# bpf-L-band-BPF-A1340.net
KiCad netlist of a schematic drawn in EAGLE
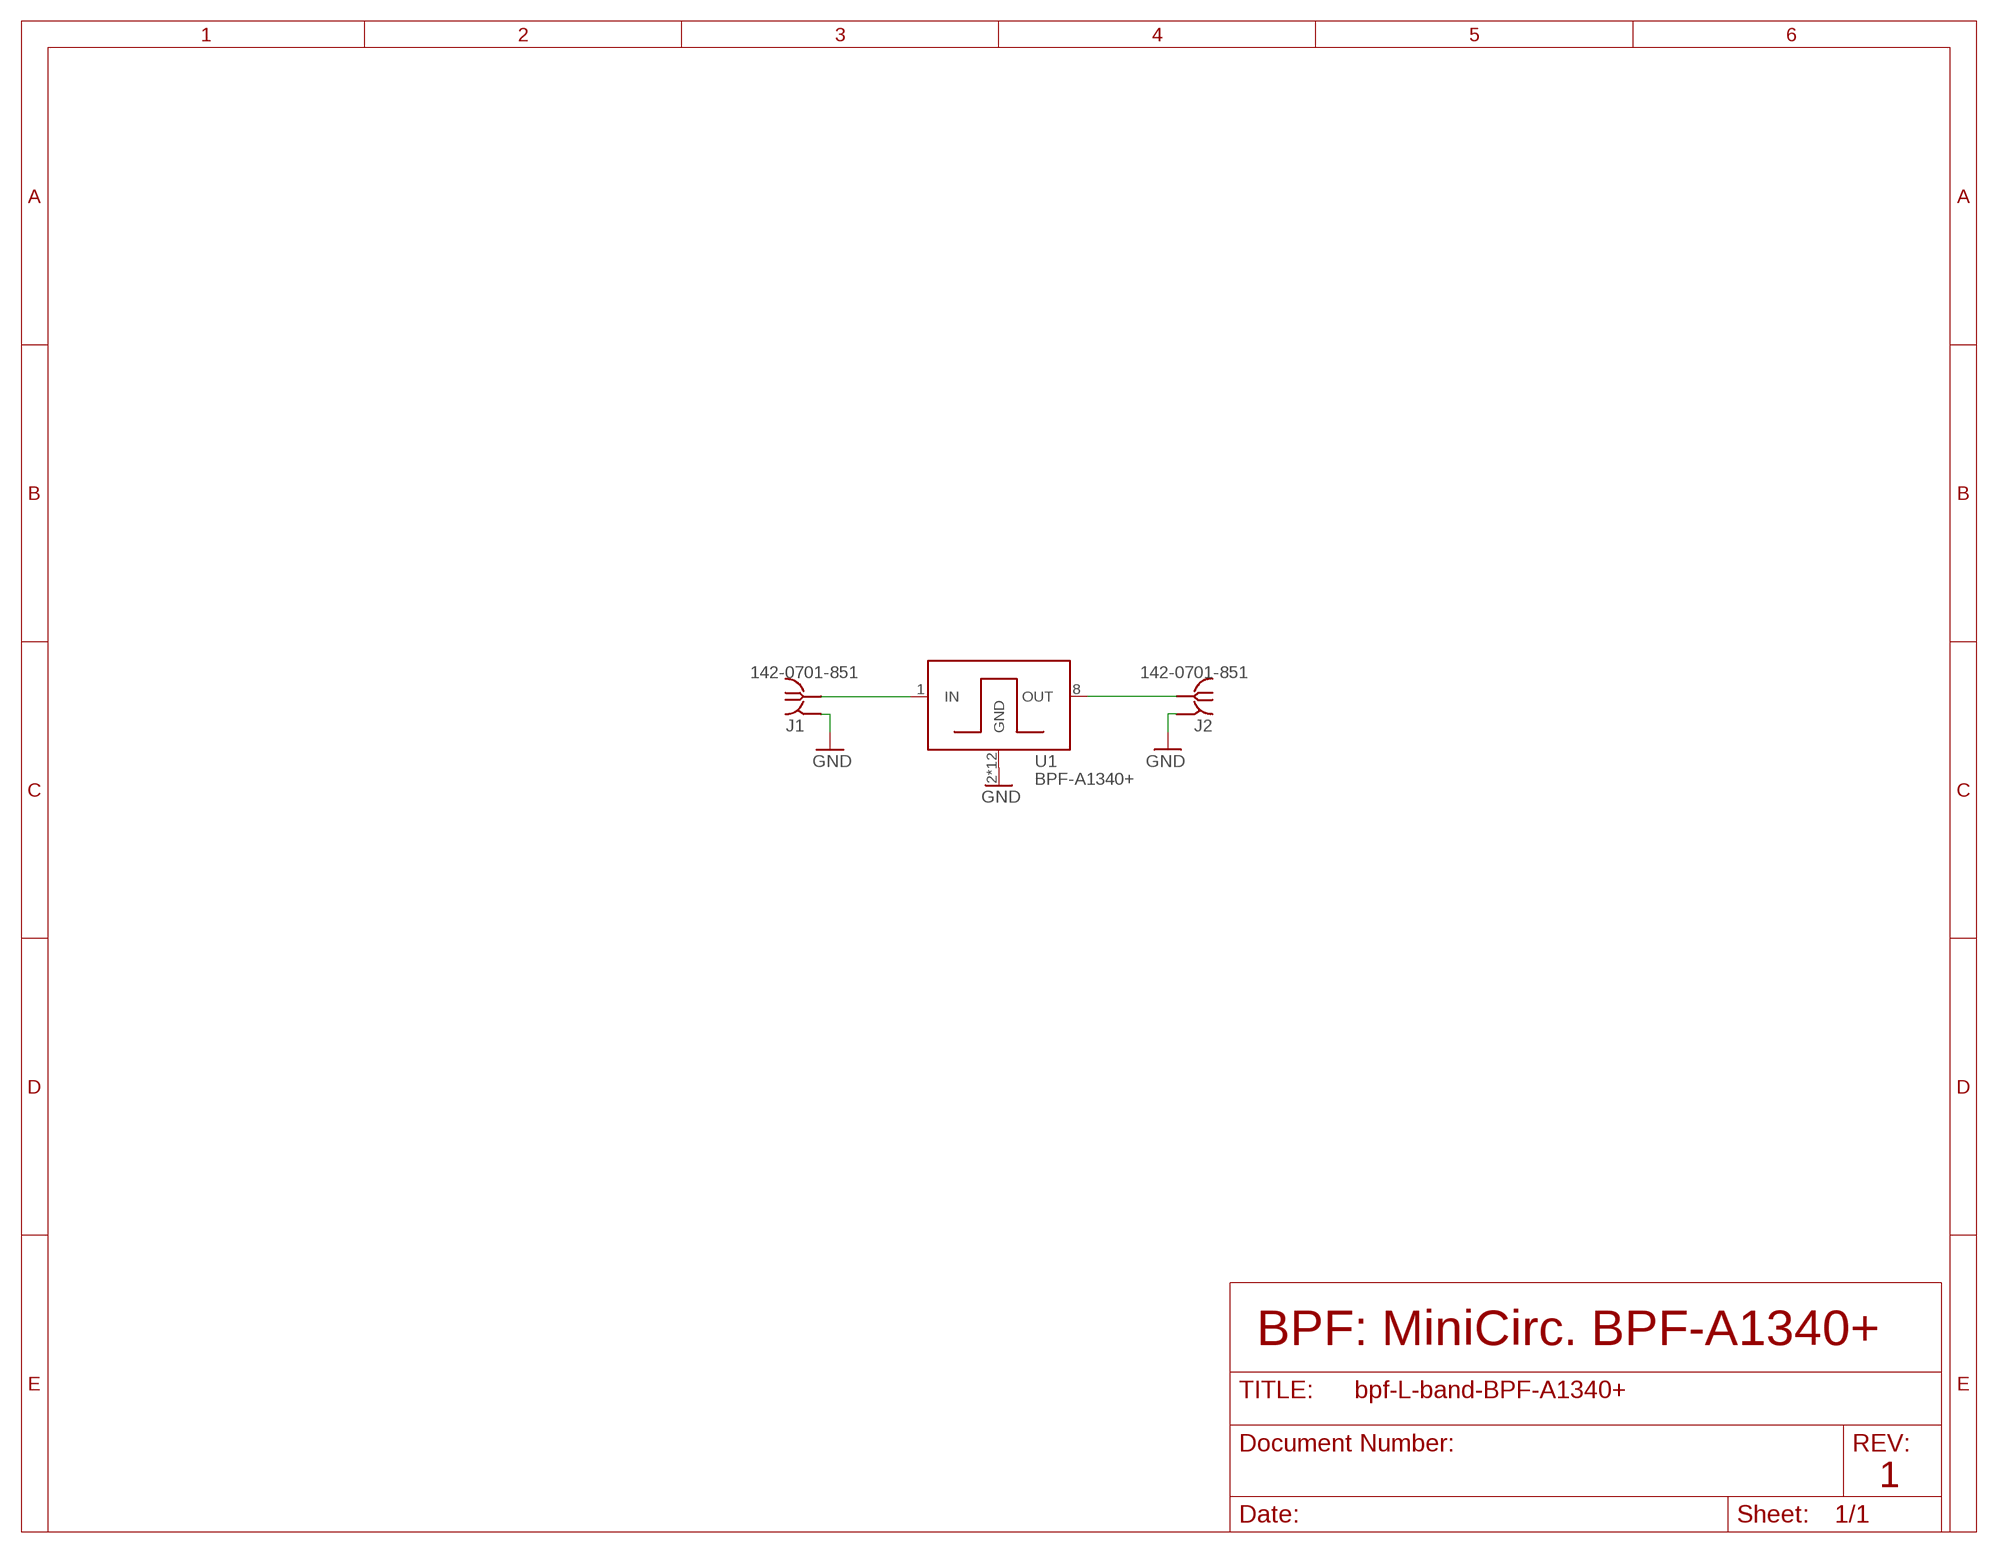
[diagram p0: schematic, sheet 1]

(export (version "E")
  (design (tool "Eeschema 10.0.6"))
  (components
    (comp (ref "J1")
      (value "142-0701-851")
      (footprint "eagle-import:142-0701-851")
      (libsource (lib "eagle-import") (part "142-0701-851"))
    )
    (comp (ref "J2")
      (value "142-0701-851")
      (footprint "eagle-import:142-0701-851")
      (libsource (lib "eagle-import") (part "142-0701-851"))
    )
    (comp (ref "U1")
      (value "BPF-A1340+")
      (footprint "eagle-import:BPF-A1340+")
      (libsource (lib "eagle-import") (part "BPF-A1340+"))
    )
  )
  (nets
    (net (code "1") (name "GND") (class "Default")
      (node (ref "J1") (pin "GND1") (pinfunction "GND_GND1") (pintype "bidirectional"))
      (node (ref "J1") (pin "GND2") (pinfunction "GND_GND2") (pintype "bidirectional"))
      (node (ref "J1") (pin "GND3") (pinfunction "GND_GND3") (pintype "bidirectional"))
      (node (ref "J1") (pin "GND4") (pinfunction "GND_GND4") (pintype "bidirectional"))
      (node (ref "J2") (pin "GND1") (pinfunction "GND_GND1") (pintype "bidirectional"))
      (node (ref "J2") (pin "GND2") (pinfunction "GND_GND2") (pintype "bidirectional"))
      (node (ref "J2") (pin "GND3") (pinfunction "GND_GND3") (pintype "bidirectional"))
      (node (ref "J2") (pin "GND4") (pinfunction "GND_GND4") (pintype "bidirectional"))
      (node (ref "U1") (pin "10") (pinfunction "GND_10") (pintype "power_in"))
      (node (ref "U1") (pin "11") (pinfunction "GND_11") (pintype "power_in"))
      (node (ref "U1") (pin "12") (pinfunction "GND_12") (pintype "power_in"))
      (node (ref "U1") (pin "13") (pinfunction "GND_13") (pintype "power_in"))
      (node (ref "U1") (pin "14") (pinfunction "GND_14") (pintype "power_in"))
      (node (ref "U1") (pin "2") (pinfunction "GND_2") (pintype "power_in"))
      (node (ref "U1") (pin "3") (pinfunction "GND_3") (pintype "power_in"))
      (node (ref "U1") (pin "4") (pinfunction "GND_4") (pintype "power_in"))
      (node (ref "U1") (pin "5") (pinfunction "GND_5") (pintype "power_in"))
      (node (ref "U1") (pin "6") (pinfunction "GND_6") (pintype "power_in"))
      (node (ref "U1") (pin "7") (pinfunction "GND_7") (pintype "power_in"))
      (node (ref "U1") (pin "9") (pinfunction "GND_9") (pintype "power_in"))
    )
    (net (code "2") (name "Net-(J1-RF)") (class "Default")
      (node (ref "J1") (pin "RF1") (pinfunction "RF_RF1") (pintype "bidirectional"))
      (node (ref "U1") (pin "1") (pinfunction "IN_1") (pintype "input"))
    )
    (net (code "3") (name "Net-(J2-RF)") (class "Default")
      (node (ref "J2") (pin "RF1") (pinfunction "RF_RF1") (pintype "bidirectional"))
      (node (ref "U1") (pin "8") (pinfunction "OUT_8") (pintype "output"))
    )
  )
)
